# mini_breadboard.net
KiCad netlist of a schematic drawn in Altium Designer
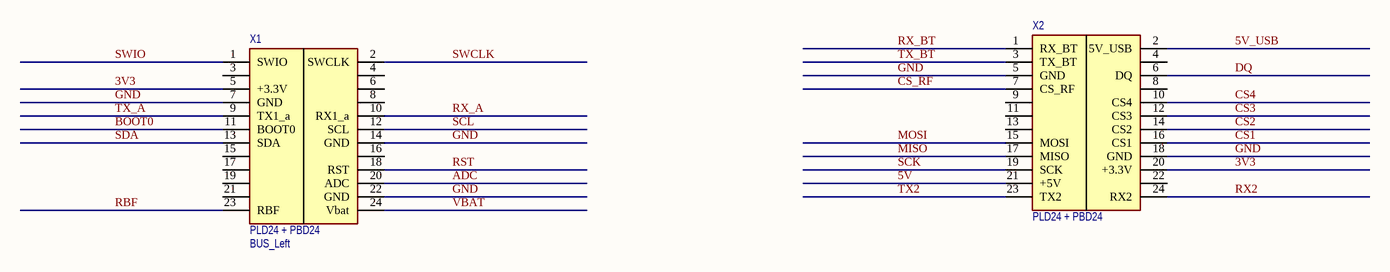
[diagram p0: mini_breadboard.SchDoc]

(export (version "E")
  (design (tool "Eeschema 10.0.6"))
  (components
    (comp (ref "X1")
      (value "PLD24 + PBD24")
      (footprint "PICOSAT_CNN")
      (description "10x2 header")
      (fields (field (name "PURPOSE") "BUS_Left"))
      (libsource (lib "connectors") (part "Header 2x12"))
    )
    (comp (ref "X2")
      (value "PLD24 + PBD24")
      (footprint "PICOSAT_CNN")
      (description "10x2 header")
      (libsource (lib "connectors") (part "Header 2x12"))
    )
  )
  (nets
    (net (code "1") (name "/3V3") (class "Default")
      (node (ref "X1") (pin "5") (pinfunction "+3.3V_5") (pintype "passive"))
      (node (ref "X2") (pin "20") (pinfunction "ADC_20") (pintype "passive"))
    )
    (net (code "2") (name "/5V") (class "Default") (node (ref "X2") (pin "21") (pintype "passive")))
    (net (code "3") (name "/5V_USB") (class "Default")
      (node (ref "X2") (pin "2") (pinfunction "SWCLK_2") (pintype "passive"))
    )
    (net (code "4") (name "/ADC") (class "Default")
      (node (ref "X1") (pin "20") (pinfunction "ADC_20") (pintype "passive"))
    )
    (net (code "5") (name "/BOOT0") (class "Default")
      (node (ref "X1") (pin "11") (pinfunction "BOOT0_11") (pintype "passive"))
    )
    (net (code "6") (name "/CS1") (class "Default") (node (ref "X2") (pin "16") (pintype "passive")))
    (net (code "7") (name "/CS2") (class "Default")
      (node (ref "X2") (pin "14") (pinfunction "GND_14") (pintype "passive"))
    )
    (net (code "8") (name "/CS3") (class "Default")
      (node (ref "X2") (pin "12") (pinfunction "SCL_12") (pintype "passive"))
    )
    (net (code "9") (name "/CS4") (class "Default")
      (node (ref "X2") (pin "10") (pinfunction "RX1_a_10") (pintype "passive"))
    )
    (net (code "10") (name "/CS_RF") (class "Default")
      (node (ref "X2") (pin "7") (pinfunction "GND_7") (pintype "passive"))
    )
    (net (code "11") (name "/DQ") (class "Default") (node (ref "X2") (pin "6") (pintype "passive")))
    (net (code "12") (name "/GND") (class "Default")
      (node (ref "X1") (pin "14") (pinfunction "GND_14") (pintype "passive"))
      (node (ref "X1") (pin "22") (pinfunction "GND_22") (pintype "passive"))
      (node (ref "X1") (pin "7") (pinfunction "GND_7") (pintype "passive"))
      (node (ref "X2") (pin "18") (pinfunction "RST_18") (pintype "passive"))
      (node (ref "X2") (pin "5") (pinfunction "+3.3V_5") (pintype "passive"))
    )
    (net (code "13") (name "/MISO") (class "Default") (node (ref "X2") (pin "17") (pintype "passive")))
    (net (code "14") (name "/MOSI") (class "Default") (node (ref "X2") (pin "15") (pintype "passive")))
    (net (code "15") (name "/RBF") (class "Default")
      (node (ref "X1") (pin "23") (pinfunction "RBF_23") (pintype "passive"))
    )
    (net (code "16") (name "/RST") (class "Default")
      (node (ref "X1") (pin "18") (pinfunction "RST_18") (pintype "passive"))
    )
    (net (code "17") (name "/RX2") (class "Default")
      (node (ref "X2") (pin "24") (pinfunction "Vbat_24") (pintype "passive"))
    )
    (net (code "18") (name "/RX_A") (class "Default")
      (node (ref "X1") (pin "10") (pinfunction "RX1_a_10") (pintype "passive"))
    )
    (net (code "19") (name "/RX_BT") (class "Default")
      (node (ref "X2") (pin "1") (pinfunction "SWIO_1") (pintype "passive"))
    )
    (net (code "20") (name "/SCK") (class "Default") (node (ref "X2") (pin "19") (pintype "passive")))
    (net (code "21") (name "/SCL") (class "Default")
      (node (ref "X1") (pin "12") (pinfunction "SCL_12") (pintype "passive"))
    )
    (net (code "22") (name "/SDA") (class "Default")
      (node (ref "X1") (pin "13") (pinfunction "SDA_13") (pintype "passive"))
    )
    (net (code "23") (name "/SWCLK") (class "Default")
      (node (ref "X1") (pin "2") (pinfunction "SWCLK_2") (pintype "passive"))
    )
    (net (code "24") (name "/SWIO") (class "Default")
      (node (ref "X1") (pin "1") (pinfunction "SWIO_1") (pintype "passive"))
    )
    (net (code "25") (name "/TX2") (class "Default")
      (node (ref "X2") (pin "23") (pinfunction "RBF_23") (pintype "passive"))
    )
    (net (code "26") (name "/TX_A") (class "Default")
      (node (ref "X1") (pin "9") (pinfunction "TX1_a_9") (pintype "passive"))
    )
    (net (code "27") (name "/TX_BT") (class "Default") (node (ref "X2") (pin "3") (pintype "passive")))
    (net (code "28") (name "/VBAT") (class "Default")
      (node (ref "X1") (pin "24") (pinfunction "Vbat_24") (pintype "passive"))
    )
    (net (code "29") (name "unconnected-(X1-Pad3)") (class "Default")
      (node (ref "X1") (pin "3") (pintype "passive"))
    )
    (net (code "30") (name "unconnected-(X1-Pad4)") (class "Default")
      (node (ref "X1") (pin "4") (pintype "passive"))
    )
    (net (code "31") (name "unconnected-(X1-Pad6)") (class "Default")
      (node (ref "X1") (pin "6") (pintype "passive"))
    )
    (net (code "32") (name "unconnected-(X1-Pad8)") (class "Default")
      (node (ref "X1") (pin "8") (pintype "passive"))
    )
    (net (code "33") (name "unconnected-(X1-Pad15)") (class "Default")
      (node (ref "X1") (pin "15") (pintype "passive"))
    )
    (net (code "34") (name "unconnected-(X1-Pad16)") (class "Default")
      (node (ref "X1") (pin "16") (pintype "passive"))
    )
    (net (code "35") (name "unconnected-(X1-Pad17)") (class "Default")
      (node (ref "X1") (pin "17") (pintype "passive"))
    )
    (net (code "36") (name "unconnected-(X1-Pad19)") (class "Default")
      (node (ref "X1") (pin "19") (pintype "passive"))
    )
    (net (code "37") (name "unconnected-(X1-Pad21)") (class "Default")
      (node (ref "X1") (pin "21") (pintype "passive"))
    )
    (net (code "38") (name "unconnected-(X2-BOOT0-Pad11)") (class "Default")
      (node (ref "X2") (pin "11") (pinfunction "BOOT0_11") (pintype "passive"))
    )
    (net (code "39") (name "unconnected-(X2-GND-Pad22)") (class "Default")
      (node (ref "X2") (pin "22") (pinfunction "GND_22") (pintype "passive"))
    )
    (net (code "40") (name "unconnected-(X2-Pad4)") (class "Default")
      (node (ref "X2") (pin "4") (pintype "passive"))
    )
    (net (code "41") (name "unconnected-(X2-Pad8)") (class "Default")
      (node (ref "X2") (pin "8") (pintype "passive"))
    )
    (net (code "42") (name "unconnected-(X2-SDA-Pad13)") (class "Default")
      (node (ref "X2") (pin "13") (pinfunction "SDA_13") (pintype "passive"))
    )
    (net (code "43") (name "unconnected-(X2-TX1_a-Pad9)") (class "Default")
      (node (ref "X2") (pin "9") (pinfunction "TX1_a_9") (pintype "passive"))
    )
  )
)
